# M8341X2.net
KiCad netlist of a schematic drawn in EAGLE
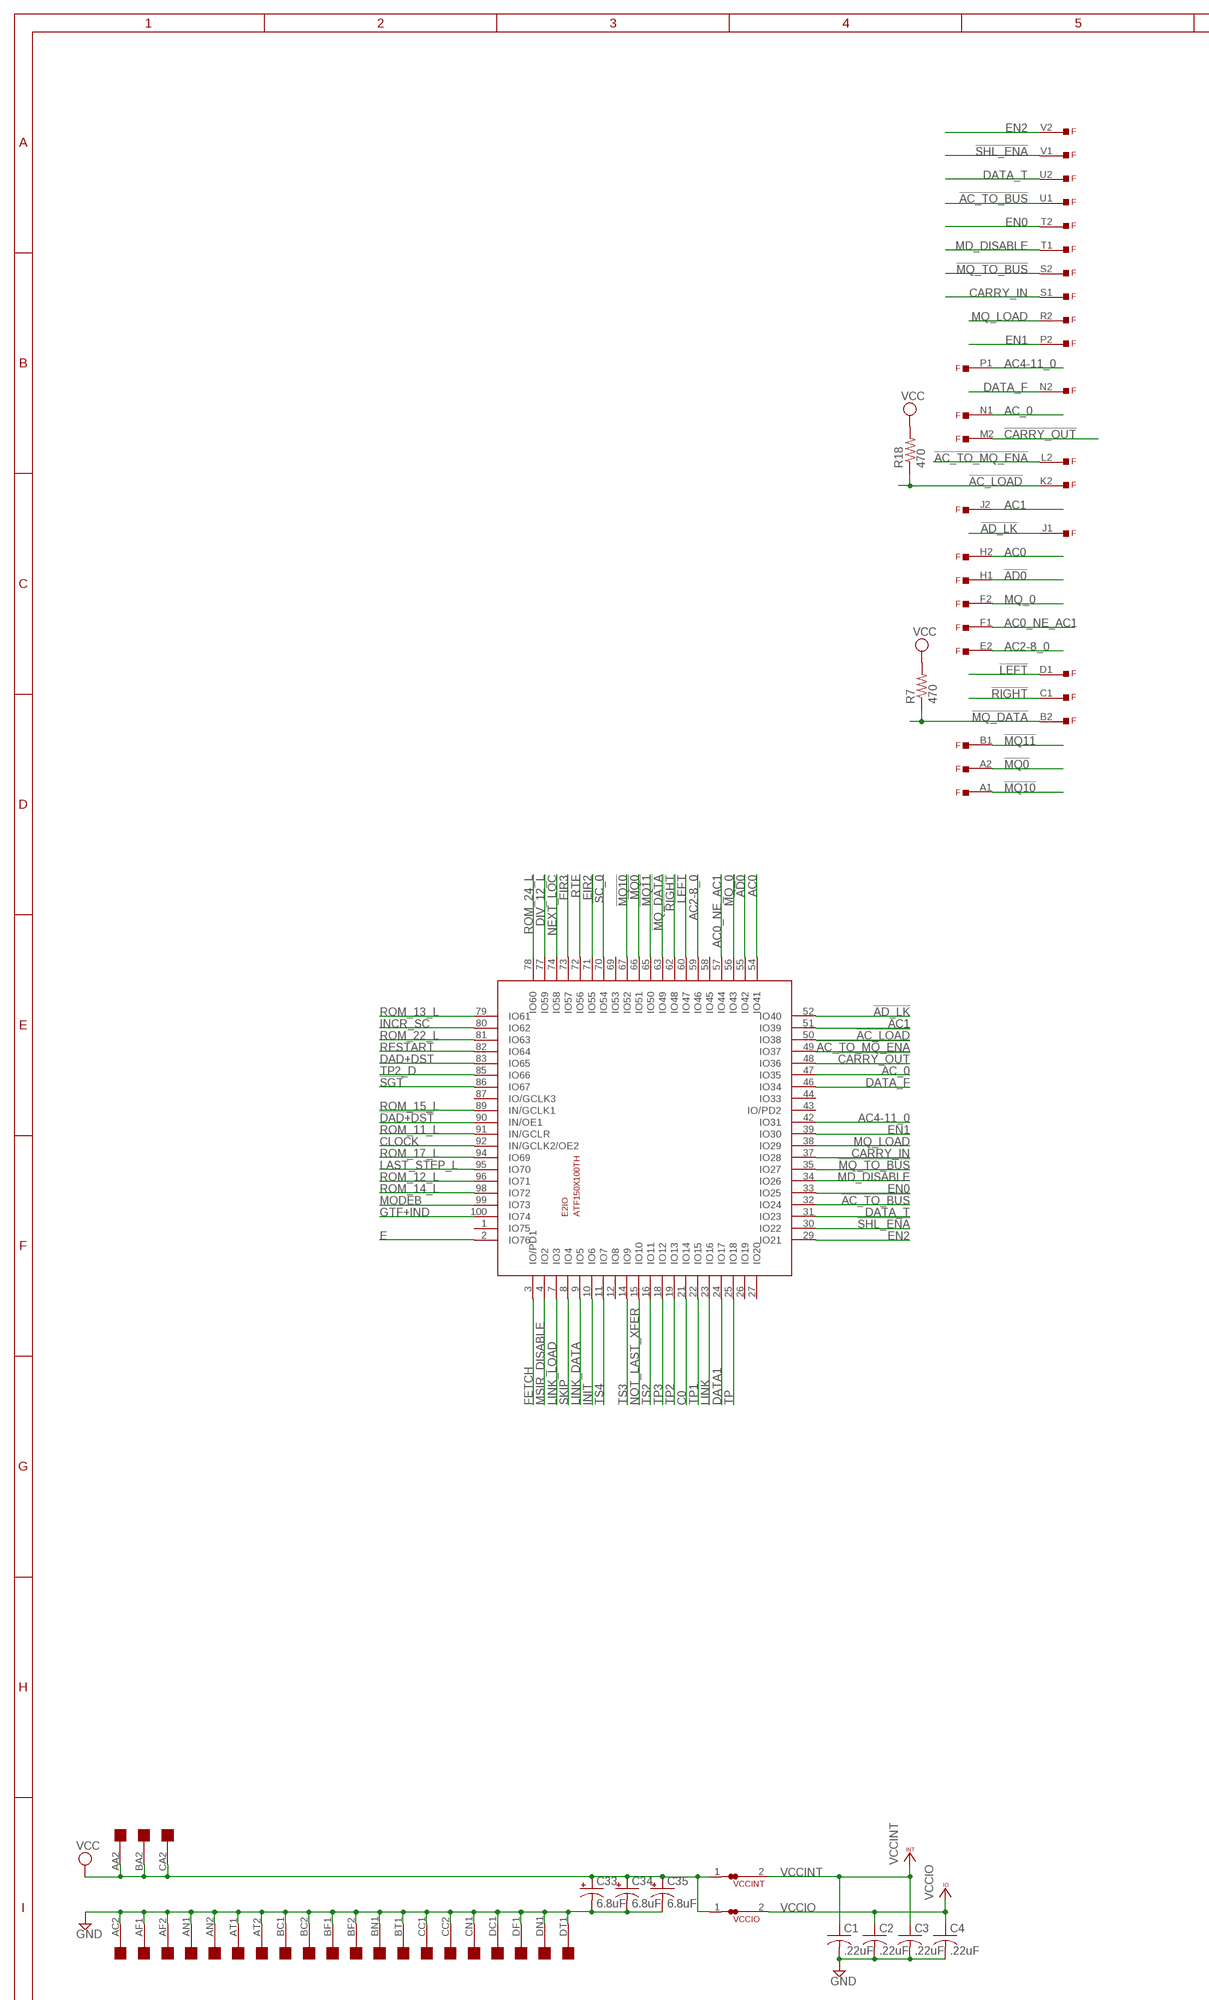
[diagram p0: schematic, sheet 1, part 1 of 2]
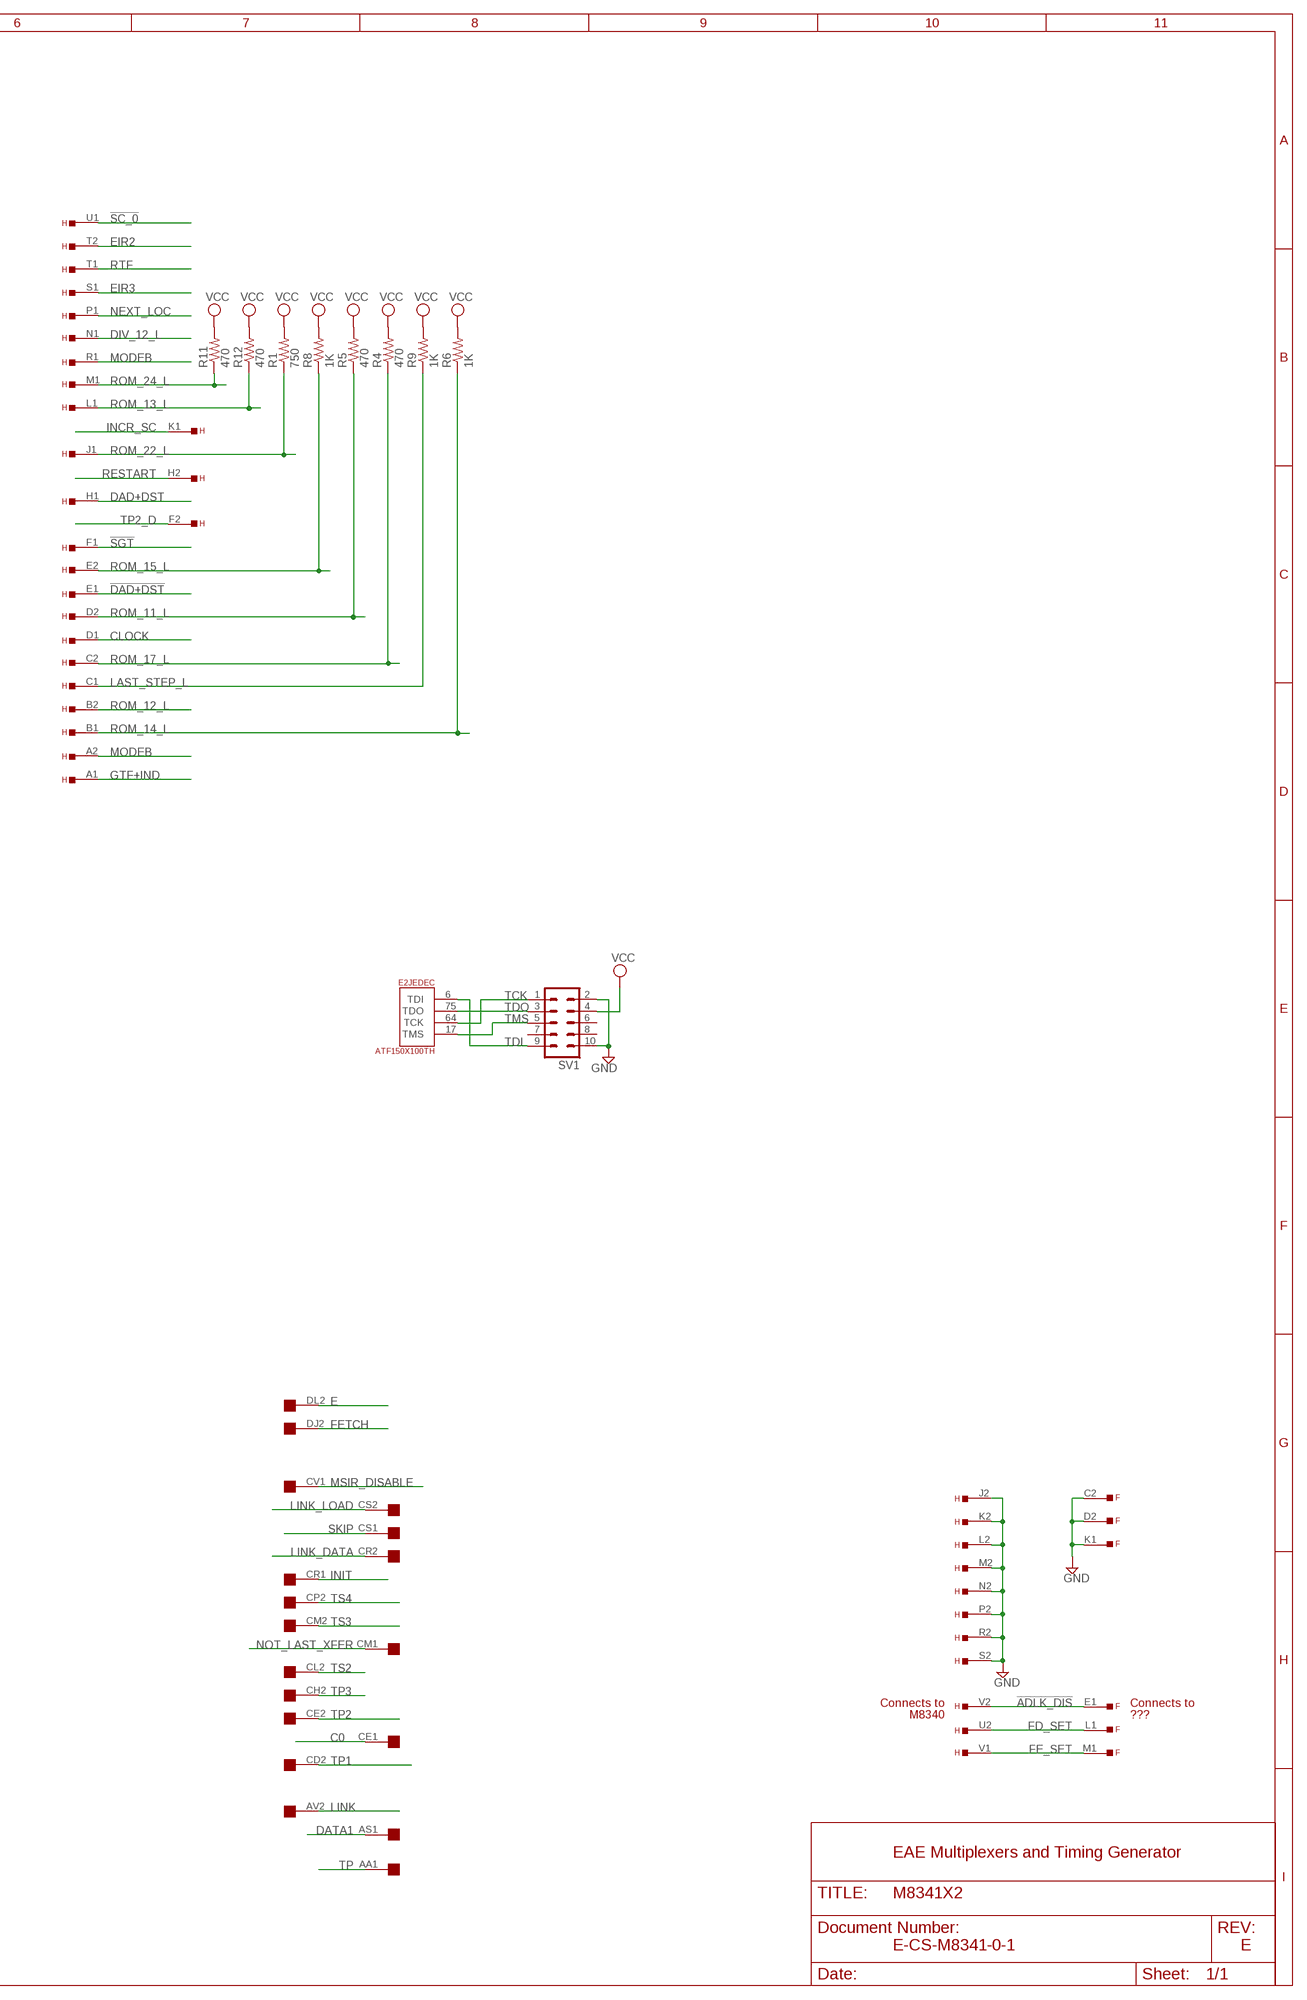
[diagram p1: schematic, sheet 1, part 2 of 2]

(export (version "E")
  (design (tool "Eeschema 10.0.6"))
  (components
    (comp (ref "C1")
      (value ".22uF")
      (footprint "eagle-import:C063-025X075")
      (libsource (lib "eagle-import") (part "C-US"))
    )
    (comp (ref "C2")
      (value ".22uF")
      (footprint "eagle-import:C063-025X075")
      (libsource (lib "eagle-import") (part "C-US"))
    )
    (comp (ref "C3")
      (value ".22uF")
      (footprint "eagle-import:C063-025X075")
      (libsource (lib "eagle-import") (part "C-US"))
    )
    (comp (ref "C4")
      (value ".22uF")
      (footprint "eagle-import:C063-025X075")
      (libsource (lib "eagle-import") (part "C-US"))
    )
    (comp (ref "C33")
      (value "6.8uF")
      (footprint "eagle-import:E12-8")
      (libsource (lib "eagle-import") (part "CPOL-USE20-8AXIAL"))
    )
    (comp (ref "C34")
      (value "6.8uF")
      (footprint "eagle-import:E12-8")
      (libsource (lib "eagle-import") (part "CPOL-USE20-8AXIAL"))
    )
    (comp (ref "C35")
      (value "6.8uF")
      (footprint "eagle-import:E12-8")
      (libsource (lib "eagle-import") (part "CPOL-USE20-8AXIAL"))
    )
    (comp (ref "E2")
      (value "ATF150X100TH")
      (footprint "eagle-import:TH-100")
      (libsource (lib "eagle-import") (part "ATF150X100TH"))
    )
    (comp (ref "F")
      (value "EDGE-TOP")
      (footprint "eagle-import:EDGE-CON2")
      (libsource (lib "eagle-import") (part "EDGE-TOP"))
    )
    (comp (ref "H")
      (value "EDGE-TOP")
      (footprint "eagle-import:EDGE-CON2")
      (libsource (lib "eagle-import") (part "EDGE-TOP"))
    )
    (comp (ref "R1")
      (value "750")
      (footprint "eagle-import:0207_10")
      (libsource (lib "eagle-import") (part "R-US_0207/10"))
    )
    (comp (ref "R4")
      (value "470")
      (footprint "eagle-import:0207_10")
      (libsource (lib "eagle-import") (part "R-US_0207/10"))
    )
    (comp (ref "R5")
      (value "470")
      (footprint "eagle-import:0207_10")
      (libsource (lib "eagle-import") (part "R-US_0207/10"))
    )
    (comp (ref "R6")
      (value "1K")
      (footprint "eagle-import:0207_10")
      (libsource (lib "eagle-import") (part "R-US_0207/10"))
    )
    (comp (ref "R7")
      (value "470")
      (footprint "eagle-import:0207_10")
      (libsource (lib "eagle-import") (part "R-US_0207/10"))
    )
    (comp (ref "R8")
      (value "1K")
      (footprint "eagle-import:0207_10")
      (libsource (lib "eagle-import") (part "R-US_0207/10"))
    )
    (comp (ref "R9")
      (value "1K")
      (footprint "eagle-import:0207_10")
      (libsource (lib "eagle-import") (part "R-US_0207/10"))
    )
    (comp (ref "R11")
      (value "470")
      (footprint "eagle-import:0207_10")
      (libsource (lib "eagle-import") (part "R-US_0207/10"))
    )
    (comp (ref "R12")
      (value "470")
      (footprint "eagle-import:0207_10")
      (libsource (lib "eagle-import") (part "R-US_0207/10"))
    )
    (comp (ref "R18")
      (value "470")
      (footprint "eagle-import:0207_10")
      (libsource (lib "eagle-import") (part "R-US_0207/10"))
    )
    (comp (ref "SV1")
      (value "ML10")
      (footprint "eagle-import:ML10")
      (libsource (lib "eagle-import") (part "ML10"))
    )
    (comp (ref "U$2")
      (value "QUAD")
      (footprint "eagle-import:EDGE-CON8")
      (libsource (lib "eagle-import") (part "QUAD"))
    )
    (comp (ref "VCCINT")
      (value "JUMPER-NC1")
      (footprint "eagle-import:NC1")
      (libsource (lib "eagle-import") (part "JUMPER-NC1"))
    )
    (comp (ref "VCCIO")
      (value "JUMPER-NC1")
      (footprint "eagle-import:NC1")
      (libsource (lib "eagle-import") (part "JUMPER-NC1"))
    )
  )
  (nets
    (net (code "1") (name "/AC0") (class "Default")
      (node (ref "E2") (pin "54") (pinfunction "IO41_54") (pintype "bidirectional"))
      (node (ref "F") (pin "H2") (pinfunction "P_H2") (pintype "passive"))
    )
    (net (code "2") (name "/AC0_NE_AC1") (class "Default")
      (node (ref "E2") (pin "57") (pinfunction "IO44_57") (pintype "bidirectional"))
      (node (ref "F") (pin "F1") (pinfunction "P_F1") (pintype "passive"))
    )
    (net (code "3") (name "/AC1") (class "Default")
      (node (ref "E2") (pin "51") (pinfunction "IO39_51") (pintype "bidirectional"))
      (node (ref "F") (pin "J2") (pinfunction "P_J2") (pintype "passive"))
    )
    (net (code "4") (name "/AC2-8_0") (class "Default")
      (node (ref "E2") (pin "59") (pinfunction "IO46_59") (pintype "bidirectional"))
      (node (ref "F") (pin "E2") (pinfunction "P_E2") (pintype "passive"))
    )
    (net (code "5") (name "/AC4-11_0") (class "Default")
      (node (ref "E2") (pin "42") (pinfunction "IO31_42") (pintype "bidirectional"))
      (node (ref "F") (pin "P1") (pinfunction "P_P1") (pintype "passive"))
    )
    (net (code "6") (name "/AC_0") (class "Default")
      (node (ref "E2") (pin "47") (pinfunction "IO35_47") (pintype "bidirectional"))
      (node (ref "F") (pin "N1") (pinfunction "P_N1") (pintype "passive"))
    )
    (net (code "7") (name "/C0") (class "Default")
      (node (ref "E2") (pin "21") (pinfunction "IO14_21") (pintype "bidirectional"))
      (node (ref "U$2") (pin "CE1") (pinfunction "1_CE1") (pintype "bidirectional"))
    )
    (net (code "8") (name "/CARRY_IN") (class "Default")
      (node (ref "E2") (pin "37") (pinfunction "IO28_37") (pintype "bidirectional"))
      (node (ref "F") (pin "S1") (pinfunction "P_S1") (pintype "passive"))
    )
    (net (code "9") (name "/CLOCK") (class "Default")
      (node (ref "E2") (pin "92") (pinfunction "IN/GCLK2/OE2_92") (pintype "input"))
      (node (ref "H") (pin "D1") (pinfunction "P_D1") (pintype "passive"))
    )
    (net (code "10") (name "/DAD+DST") (class "Default")
      (node (ref "E2") (pin "83") (pinfunction "IO65_83") (pintype "bidirectional"))
      (node (ref "H") (pin "H1") (pinfunction "P_H1") (pintype "passive"))
    )
    (net (code "11") (name "/DATA1") (class "Default")
      (node (ref "E2") (pin "24") (pinfunction "IO17_24") (pintype "bidirectional"))
      (node (ref "U$2") (pin "AS1") (pinfunction "1_AS1") (pintype "bidirectional"))
    )
    (net (code "12") (name "/DATA_F") (class "Default")
      (node (ref "E2") (pin "46") (pinfunction "IO34_46") (pintype "bidirectional"))
      (node (ref "F") (pin "N2") (pinfunction "P_N2") (pintype "passive"))
    )
    (net (code "13") (name "/DATA_T") (class "Default")
      (node (ref "E2") (pin "31") (pinfunction "IO23_31") (pintype "bidirectional"))
      (node (ref "F") (pin "U2") (pinfunction "P_U2") (pintype "passive"))
    )
    (net (code "14") (name "/DIV_12_L") (class "Default")
      (node (ref "E2") (pin "77") (pinfunction "IO59_77") (pintype "bidirectional"))
      (node (ref "H") (pin "N1") (pinfunction "P_N1") (pintype "passive"))
    )
    (net (code "15") (name "/E") (class "Default")
      (node (ref "E2") (pin "2") (pinfunction "IO76_2") (pintype "bidirectional"))
      (node (ref "U$2") (pin "DL2") (pinfunction "1_DL2") (pintype "bidirectional"))
    )
    (net (code "16") (name "/EIR2") (class "Default")
      (node (ref "E2") (pin "71") (pinfunction "IO55_71") (pintype "bidirectional"))
      (node (ref "H") (pin "T2") (pinfunction "P_T2") (pintype "passive"))
    )
    (net (code "17") (name "/EIR3") (class "Default")
      (node (ref "E2") (pin "73") (pinfunction "IO57_73") (pintype "bidirectional"))
      (node (ref "H") (pin "S1") (pinfunction "P_S1") (pintype "passive"))
    )
    (net (code "18") (name "/EN0") (class "Default")
      (node (ref "E2") (pin "33") (pinfunction "IO25_33") (pintype "bidirectional"))
      (node (ref "F") (pin "T2") (pinfunction "P_T2") (pintype "passive"))
    )
    (net (code "19") (name "/EN1") (class "Default")
      (node (ref "E2") (pin "39") (pinfunction "IO30_39") (pintype "bidirectional"))
      (node (ref "F") (pin "P2") (pinfunction "P_P2") (pintype "passive"))
    )
    (net (code "20") (name "/EN2") (class "Default")
      (node (ref "E2") (pin "29") (pinfunction "IO21_29") (pintype "bidirectional"))
      (node (ref "F") (pin "V2") (pinfunction "P_V2") (pintype "passive"))
    )
    (net (code "21") (name "/FD_SET") (class "Default")
      (node (ref "F") (pin "L1") (pinfunction "P_L1") (pintype "passive"))
      (node (ref "H") (pin "U2") (pinfunction "P_U2") (pintype "passive"))
    )
    (net (code "22") (name "/FETCH") (class "Default")
      (node (ref "E2") (pin "3") (pinfunction "IO/PD1_3") (pintype "bidirectional"))
      (node (ref "U$2") (pin "DJ2") (pinfunction "1_DJ2") (pintype "bidirectional"))
    )
    (net (code "23") (name "/FE_SET") (class "Default")
      (node (ref "F") (pin "M1") (pinfunction "P_M1") (pintype "passive"))
      (node (ref "H") (pin "V1") (pinfunction "P_V1") (pintype "passive"))
    )
    (net (code "24") (name "/GTF+IND") (class "Default")
      (node (ref "E2") (pin "100") (pinfunction "IO74_100") (pintype "bidirectional"))
      (node (ref "H") (pin "A1") (pinfunction "P_A1") (pintype "passive"))
    )
    (net (code "25") (name "/INCR_SC") (class "Default")
      (node (ref "E2") (pin "80") (pinfunction "IO62_80") (pintype "bidirectional"))
      (node (ref "H") (pin "K1") (pinfunction "P_K1") (pintype "passive"))
    )
    (net (code "26") (name "/INIT") (class "Default")
      (node (ref "E2") (pin "10") (pinfunction "IO6_10") (pintype "bidirectional"))
      (node (ref "U$2") (pin "CR1") (pinfunction "1_CR1") (pintype "bidirectional"))
    )
    (net (code "27") (name "/LAST_STEP_L") (class "Default")
      (node (ref "E2") (pin "95") (pinfunction "IO70_95") (pintype "bidirectional"))
      (node (ref "H") (pin "C1") (pinfunction "P_C1") (pintype "passive"))
      (node (ref "R9") (pin "1") (pinfunction "1_1") (pintype "passive"))
    )
    (net (code "28") (name "/LINK") (class "Default")
      (node (ref "E2") (pin "23") (pinfunction "IO16_23") (pintype "bidirectional"))
      (node (ref "U$2") (pin "AV2") (pinfunction "1_AV2") (pintype "bidirectional"))
    )
    (net (code "29") (name "/LINK_DATA") (class "Default")
      (node (ref "E2") (pin "9") (pinfunction "IO5_9") (pintype "bidirectional"))
      (node (ref "U$2") (pin "CR2") (pinfunction "1_CR2") (pintype "bidirectional"))
    )
    (net (code "30") (name "/LINK_LOAD") (class "Default")
      (node (ref "E2") (pin "7") (pinfunction "IO3_7") (pintype "bidirectional"))
      (node (ref "U$2") (pin "CS2") (pinfunction "1_CS2") (pintype "bidirectional"))
    )
    (net (code "31") (name "/MD_DISABLE") (class "Default")
      (node (ref "E2") (pin "34") (pinfunction "IO26_34") (pintype "bidirectional"))
      (node (ref "F") (pin "T1") (pinfunction "P_T1") (pintype "passive"))
    )
    (net (code "32") (name "/MODEB") (class "Default")
      (node (ref "E2") (pin "99") (pinfunction "IO73_99") (pintype "bidirectional"))
      (node (ref "H") (pin "A2") (pinfunction "P_A2") (pintype "passive"))
      (node (ref "H") (pin "R1") (pinfunction "P_R1") (pintype "passive"))
    )
    (net (code "33") (name "/MQ_0") (class "Default")
      (node (ref "E2") (pin "56") (pinfunction "IO43_56") (pintype "bidirectional"))
      (node (ref "F") (pin "F2") (pinfunction "P_F2") (pintype "passive"))
    )
    (net (code "34") (name "/MQ_LOAD") (class "Default")
      (node (ref "E2") (pin "38") (pinfunction "IO29_38") (pintype "bidirectional"))
      (node (ref "F") (pin "R2") (pinfunction "P_R2") (pintype "passive"))
    )
    (net (code "35") (name "/MSIR_DISABLE") (class "Default")
      (node (ref "E2") (pin "4") (pinfunction "IO2_4") (pintype "bidirectional"))
      (node (ref "U$2") (pin "CV1") (pinfunction "1_CV1") (pintype "bidirectional"))
    )
    (net (code "36") (name "/NEXT_LOC") (class "Default")
      (node (ref "E2") (pin "74") (pinfunction "IO58_74") (pintype "bidirectional"))
      (node (ref "H") (pin "P1") (pinfunction "P_P1") (pintype "passive"))
    )
    (net (code "37") (name "/NOT_LAST_XFER") (class "Default")
      (node (ref "E2") (pin "15") (pinfunction "IO10_15") (pintype "bidirectional"))
      (node (ref "U$2") (pin "CM1") (pinfunction "1_CM1") (pintype "bidirectional"))
    )
    (net (code "38") (name "/RESTART") (class "Default")
      (node (ref "E2") (pin "82") (pinfunction "IO64_82") (pintype "bidirectional"))
      (node (ref "H") (pin "H2") (pinfunction "P_H2") (pintype "passive"))
    )
    (net (code "39") (name "/ROM_11_L") (class "Default")
      (node (ref "E2") (pin "91") (pinfunction "IN/GCLR_91") (pintype "input"))
      (node (ref "H") (pin "D2") (pinfunction "P_D2") (pintype "passive"))
      (node (ref "R5") (pin "1") (pinfunction "1_1") (pintype "passive"))
    )
    (net (code "40") (name "/ROM_12_L") (class "Default")
      (node (ref "E2") (pin "96") (pinfunction "IO71_96") (pintype "bidirectional"))
      (node (ref "H") (pin "B2") (pinfunction "P_B2") (pintype "passive"))
    )
    (net (code "41") (name "/ROM_13_L") (class "Default")
      (node (ref "E2") (pin "79") (pinfunction "IO61_79") (pintype "bidirectional"))
      (node (ref "H") (pin "L1") (pinfunction "P_L1") (pintype "passive"))
      (node (ref "R12") (pin "1") (pinfunction "1_1") (pintype "passive"))
    )
    (net (code "42") (name "/ROM_14_L") (class "Default")
      (node (ref "E2") (pin "98") (pinfunction "IO72_98") (pintype "bidirectional"))
      (node (ref "H") (pin "B1") (pinfunction "P_B1") (pintype "passive"))
      (node (ref "R6") (pin "1") (pinfunction "1_1") (pintype "passive"))
    )
    (net (code "43") (name "/ROM_15_L") (class "Default")
      (node (ref "E2") (pin "89") (pinfunction "IN/GCLK1_89") (pintype "input"))
      (node (ref "H") (pin "E2") (pinfunction "P_E2") (pintype "passive"))
      (node (ref "R8") (pin "1") (pinfunction "1_1") (pintype "passive"))
    )
    (net (code "44") (name "/ROM_17_L") (class "Default")
      (node (ref "E2") (pin "94") (pinfunction "IO69_94") (pintype "bidirectional"))
      (node (ref "H") (pin "C2") (pinfunction "P_C2") (pintype "passive"))
      (node (ref "R4") (pin "1") (pinfunction "1_1") (pintype "passive"))
    )
    (net (code "45") (name "/ROM_22_L") (class "Default")
      (node (ref "E2") (pin "81") (pinfunction "IO63_81") (pintype "bidirectional"))
      (node (ref "H") (pin "J1") (pinfunction "P_J1") (pintype "passive"))
      (node (ref "R1") (pin "1") (pinfunction "1_1") (pintype "passive"))
    )
    (net (code "46") (name "/ROM_24_L") (class "Default")
      (node (ref "E2") (pin "78") (pinfunction "IO60_78") (pintype "bidirectional"))
      (node (ref "H") (pin "M1") (pinfunction "P_M1") (pintype "passive"))
      (node (ref "R11") (pin "1") (pinfunction "1_1") (pintype "passive"))
    )
    (net (code "47") (name "/RTF") (class "Default")
      (node (ref "E2") (pin "72") (pinfunction "IO56_72") (pintype "bidirectional"))
      (node (ref "H") (pin "T1") (pinfunction "P_T1") (pintype "passive"))
    )
    (net (code "48") (name "/SKIP") (class "Default")
      (node (ref "E2") (pin "8") (pinfunction "IO4_8") (pintype "bidirectional"))
      (node (ref "U$2") (pin "CS1") (pinfunction "1_CS1") (pintype "bidirectional"))
    )
    (net (code "49") (name "/TCK") (class "Default")
      (node (ref "E2") (pin "64") (pinfunction "TCK_64") (pintype "bidirectional"))
      (node (ref "SV1") (pin "1") (pinfunction "1_1") (pintype "passive"))
    )
    (net (code "50") (name "/TDI") (class "Default")
      (node (ref "E2") (pin "6") (pinfunction "TDI_6") (pintype "bidirectional"))
      (node (ref "SV1") (pin "9") (pinfunction "9_9") (pintype "passive"))
    )
    (net (code "51") (name "/TDO") (class "Default")
      (node (ref "E2") (pin "75") (pinfunction "TDO_75") (pintype "bidirectional"))
      (node (ref "SV1") (pin "3") (pinfunction "3_3") (pintype "passive"))
    )
    (net (code "52") (name "/TMS") (class "Default")
      (node (ref "E2") (pin "17") (pinfunction "TMS_17") (pintype "bidirectional"))
      (node (ref "SV1") (pin "5") (pinfunction "5_5") (pintype "passive"))
    )
    (net (code "53") (name "/TP") (class "Default")
      (node (ref "E2") (pin "25") (pinfunction "IO18_25") (pintype "bidirectional"))
      (node (ref "U$2") (pin "AA1") (pinfunction "1_AA1") (pintype "bidirectional"))
    )
    (net (code "54") (name "/TP1") (class "Default")
      (node (ref "E2") (pin "22") (pinfunction "IO15_22") (pintype "bidirectional"))
      (node (ref "U$2") (pin "CD2") (pinfunction "1_CD2") (pintype "bidirectional"))
    )
    (net (code "55") (name "/TP2") (class "Default")
      (node (ref "E2") (pin "19") (pinfunction "IO13_19") (pintype "bidirectional"))
      (node (ref "U$2") (pin "CE2") (pinfunction "1_CE2") (pintype "bidirectional"))
    )
    (net (code "56") (name "/TP2_D") (class "Default")
      (node (ref "E2") (pin "85") (pinfunction "IO66_85") (pintype "bidirectional"))
      (node (ref "H") (pin "F2") (pinfunction "P_F2") (pintype "passive"))
    )
    (net (code "57") (name "/TP3") (class "Default")
      (node (ref "E2") (pin "18") (pinfunction "IO12_18") (pintype "bidirectional"))
      (node (ref "U$2") (pin "CH2") (pinfunction "1_CH2") (pintype "bidirectional"))
    )
    (net (code "58") (name "/TS2") (class "Default")
      (node (ref "E2") (pin "16") (pinfunction "IO11_16") (pintype "bidirectional"))
      (node (ref "U$2") (pin "CL2") (pinfunction "1_CL2") (pintype "bidirectional"))
    )
    (net (code "59") (name "/TS3") (class "Default")
      (node (ref "E2") (pin "14") (pinfunction "IO9_14") (pintype "bidirectional"))
      (node (ref "U$2") (pin "CM2") (pinfunction "1_CM2") (pintype "bidirectional"))
    )
    (net (code "60") (name "/TS4") (class "Default")
      (node (ref "E2") (pin "11") (pinfunction "IO7_11") (pintype "bidirectional"))
      (node (ref "U$2") (pin "CP2") (pinfunction "1_CP2") (pintype "bidirectional"))
    )
    (net (code "61") (name "/~{AC_LOAD}") (class "Default")
      (node (ref "E2") (pin "50") (pinfunction "IO38_50") (pintype "bidirectional"))
      (node (ref "F") (pin "K2") (pinfunction "P_K2") (pintype "passive"))
      (node (ref "R18") (pin "1") (pinfunction "1_1") (pintype "passive"))
    )
    (net (code "62") (name "/~{AC_TO_BUS}") (class "Default")
      (node (ref "E2") (pin "32") (pinfunction "IO24_32") (pintype "bidirectional"))
      (node (ref "F") (pin "U1") (pinfunction "P_U1") (pintype "passive"))
    )
    (net (code "63") (name "/~{AC_TO_MQ_ENA}") (class "Default")
      (node (ref "E2") (pin "49") (pinfunction "IO37_49") (pintype "bidirectional"))
      (node (ref "F") (pin "L2") (pinfunction "P_L2") (pintype "passive"))
    )
    (net (code "64") (name "/~{AD0}") (class "Default")
      (node (ref "E2") (pin "55") (pinfunction "IO42_55") (pintype "bidirectional"))
      (node (ref "F") (pin "H1") (pinfunction "P_H1") (pintype "passive"))
    )
    (net (code "65") (name "/~{ADLK_DIS}") (class "Default")
      (node (ref "F") (pin "E1") (pinfunction "P_E1") (pintype "passive"))
      (node (ref "H") (pin "V2") (pinfunction "P_V2") (pintype "passive"))
    )
    (net (code "66") (name "/~{AD_LK}") (class "Default")
      (node (ref "E2") (pin "52") (pinfunction "IO40_52") (pintype "bidirectional"))
      (node (ref "F") (pin "J1") (pinfunction "P_J1") (pintype "passive"))
    )
    (net (code "67") (name "/~{CARRY_OUT}") (class "Default")
      (node (ref "E2") (pin "48") (pinfunction "IO36_48") (pintype "bidirectional"))
      (node (ref "F") (pin "M2") (pinfunction "P_M2") (pintype "passive"))
    )
    (net (code "68") (name "/~{DAD+DST}") (class "Default")
      (node (ref "E2") (pin "90") (pinfunction "IN/OE1_90") (pintype "input"))
      (node (ref "H") (pin "E1") (pinfunction "P_E1") (pintype "passive"))
    )
    (net (code "69") (name "/~{LEFT}") (class "Default")
      (node (ref "E2") (pin "60") (pinfunction "IO47_60") (pintype "bidirectional"))
      (node (ref "F") (pin "D1") (pinfunction "P_D1") (pintype "passive"))
    )
    (net (code "70") (name "/~{MQ0}") (class "Default")
      (node (ref "E2") (pin "66") (pinfunction "IO51_66") (pintype "bidirectional"))
      (node (ref "F") (pin "A2") (pinfunction "P_A2") (pintype "passive"))
    )
    (net (code "71") (name "/~{MQ10}") (class "Default")
      (node (ref "E2") (pin "67") (pinfunction "IO52_67") (pintype "bidirectional"))
      (node (ref "F") (pin "A1") (pinfunction "P_A1") (pintype "passive"))
    )
    (net (code "72") (name "/~{MQ11}") (class "Default")
      (node (ref "E2") (pin "65") (pinfunction "IO50_65") (pintype "bidirectional"))
      (node (ref "F") (pin "B1") (pinfunction "P_B1") (pintype "passive"))
    )
    (net (code "73") (name "/~{MQ_DATA}") (class "Default")
      (node (ref "E2") (pin "63") (pinfunction "IO49_63") (pintype "bidirectional"))
      (node (ref "F") (pin "B2") (pinfunction "P_B2") (pintype "passive"))
      (node (ref "R7") (pin "1") (pinfunction "1_1") (pintype "passive"))
    )
    (net (code "74") (name "/~{MQ_TO_BUS}") (class "Default")
      (node (ref "E2") (pin "35") (pinfunction "IO27_35") (pintype "bidirectional"))
      (node (ref "F") (pin "S2") (pinfunction "P_S2") (pintype "passive"))
    )
    (net (code "75") (name "/~{RIGHT}") (class "Default")
      (node (ref "E2") (pin "62") (pinfunction "IO48_62") (pintype "bidirectional"))
      (node (ref "F") (pin "C1") (pinfunction "P_C1") (pintype "passive"))
    )
    (net (code "76") (name "/~{SC_0}") (class "Default")
      (node (ref "E2") (pin "70") (pinfunction "IO54_70") (pintype "bidirectional"))
      (node (ref "H") (pin "U1") (pinfunction "P_U1") (pintype "passive"))
    )
    (net (code "77") (name "/~{SGT}") (class "Default")
      (node (ref "E2") (pin "86") (pinfunction "IO67_86") (pintype "bidirectional"))
      (node (ref "H") (pin "F1") (pinfunction "P_F1") (pintype "passive"))
    )
    (net (code "78") (name "/~{SHL_ENA}") (class "Default")
      (node (ref "E2") (pin "30") (pinfunction "IO22_30") (pintype "bidirectional"))
      (node (ref "F") (pin "V1") (pinfunction "P_V1") (pintype "passive"))
    )
    (net (code "79") (name "GND") (class "Default")
      (node (ref "C1") (pin "2") (pinfunction "2_2") (pintype "passive"))
      (node (ref "C2") (pin "2") (pinfunction "2_2") (pintype "passive"))
      (node (ref "C3") (pin "2") (pinfunction "2_2") (pintype "passive"))
      (node (ref "C33") (pin "-") (pinfunction "-_-") (pintype "passive"))
      (node (ref "C34") (pin "-") (pinfunction "-_-") (pintype "passive"))
      (node (ref "C35") (pin "-") (pinfunction "-_-") (pintype "passive"))
      (node (ref "C4") (pin "2") (pinfunction "2_2") (pintype "passive"))
      (node (ref "F") (pin "C2") (pinfunction "P_C2") (pintype "passive"))
      (node (ref "F") (pin "D2") (pinfunction "P_D2") (pintype "passive"))
      (node (ref "F") (pin "K1") (pinfunction "P_K1") (pintype "passive"))
      (node (ref "H") (pin "J2") (pinfunction "P_J2") (pintype "passive"))
      (node (ref "H") (pin "K2") (pinfunction "P_K2") (pintype "passive"))
      (node (ref "H") (pin "L2") (pinfunction "P_L2") (pintype "passive"))
      (node (ref "H") (pin "M2") (pinfunction "P_M2") (pintype "passive"))
      (node (ref "H") (pin "N2") (pinfunction "P_N2") (pintype "passive"))
      (node (ref "H") (pin "P2") (pinfunction "P_P2") (pintype "passive"))
      (node (ref "H") (pin "R2") (pinfunction "P_R2") (pintype "passive"))
      (node (ref "H") (pin "S2") (pinfunction "P_S2") (pintype "passive"))
      (node (ref "SV1") (pin "10") (pinfunction "10_10") (pintype "passive"))
      (node (ref "SV1") (pin "2") (pinfunction "2_2") (pintype "passive"))
      (node (ref "U$2") (pin "AC2") (pinfunction "1_AC2") (pintype "bidirectional"))
      (node (ref "U$2") (pin "AF1") (pinfunction "1_AF1") (pintype "bidirectional"))
      (node (ref "U$2") (pin "AF2") (pinfunction "1_AF2") (pintype "bidirectional"))
      (node (ref "U$2") (pin "AN1") (pinfunction "1_AN1") (pintype "bidirectional"))
      (node (ref "U$2") (pin "AN2") (pinfunction "1_AN2") (pintype "bidirectional"))
      (node (ref "U$2") (pin "AT1") (pinfunction "1_AT1") (pintype "bidirectional"))
      (node (ref "U$2") (pin "AT2") (pinfunction "1_AT2") (pintype "bidirectional"))
      (node (ref "U$2") (pin "BC1") (pinfunction "1_BC1") (pintype "bidirectional"))
      (node (ref "U$2") (pin "BC2") (pinfunction "1_BC2") (pintype "bidirectional"))
      (node (ref "U$2") (pin "BF1") (pinfunction "1_BF1") (pintype "bidirectional"))
      (node (ref "U$2") (pin "BF2") (pinfunction "1_BF2") (pintype "bidirectional"))
      (node (ref "U$2") (pin "BN1") (pinfunction "1_BN1") (pintype "bidirectional"))
      (node (ref "U$2") (pin "BT1") (pinfunction "1_BT1") (pintype "bidirectional"))
      (node (ref "U$2") (pin "CC1") (pinfunction "1_CC1") (pintype "bidirectional"))
      (node (ref "U$2") (pin "CC2") (pinfunction "1_CC2") (pintype "bidirectional"))
      (node (ref "U$2") (pin "CN1") (pinfunction "1_CN1") (pintype "bidirectional"))
      (node (ref "U$2") (pin "DC1") (pinfunction "1_DC1") (pintype "bidirectional"))
      (node (ref "U$2") (pin "DF1") (pinfunction "1_DF1") (pintype "bidirectional"))
      (node (ref "U$2") (pin "DN1") (pinfunction "1_DN1") (pintype "bidirectional"))
      (node (ref "U$2") (pin "DT1") (pinfunction "1_DT1") (pintype "bidirectional"))
    )
    (net (code "80") (name "VCC") (class "Default")
      (node (ref "C33") (pin "+") (pinfunction "+_+") (pintype "passive"))
      (node (ref "C34") (pin "+") (pinfunction "+_+") (pintype "passive"))
      (node (ref "C35") (pin "+") (pinfunction "+_+") (pintype "passive"))
      (node (ref "R1") (pin "2") (pinfunction "2_2") (pintype "passive"))
      (node (ref "R11") (pin "2") (pinfunction "2_2") (pintype "passive"))
      (node (ref "R12") (pin "2") (pinfunction "2_2") (pintype "passive"))
      (node (ref "R18") (pin "2") (pinfunction "2_2") (pintype "passive"))
      (node (ref "R4") (pin "2") (pinfunction "2_2") (pintype "passive"))
      (node (ref "R5") (pin "2") (pinfunction "2_2") (pintype "passive"))
      (node (ref "R6") (pin "2") (pinfunction "2_2") (pintype "passive"))
      (node (ref "R7") (pin "2") (pinfunction "2_2") (pintype "passive"))
      (node (ref "R8") (pin "2") (pinfunction "2_2") (pintype "passive"))
      (node (ref "R9") (pin "2") (pinfunction "2_2") (pintype "passive"))
      (node (ref "SV1") (pin "4") (pinfunction "4_4") (pintype "passive"))
      (node (ref "U$2") (pin "AA2") (pinfunction "1_AA2") (pintype "bidirectional"))
      (node (ref "U$2") (pin "BA2") (pinfunction "1_BA2") (pintype "bidirectional"))
      (node (ref "U$2") (pin "CA2") (pinfunction "1_CA2") (pintype "bidirectional"))
      (node (ref "VCCINT") (pin "1") (pinfunction "1_1") (pintype "bidirectional"))
      (node (ref "VCCIO") (pin "1") (pinfunction "1_1") (pintype "bidirectional"))
    )
    (net (code "81") (name "VCCINT") (class "Default")
      (node (ref "C1") (pin "1") (pinfunction "1_1") (pintype "passive"))
      (node (ref "C3") (pin "1") (pinfunction "1_1") (pintype "passive"))
      (node (ref "VCCINT") (pin "2") (pinfunction "2_2") (pintype "bidirectional"))
    )
    (net (code "82") (name "VCCIO") (class "Default")
      (node (ref "C2") (pin "1") (pinfunction "1_1") (pintype "passive"))
      (node (ref "C4") (pin "1") (pinfunction "1_1") (pintype "passive"))
      (node (ref "VCCIO") (pin "2") (pinfunction "2_2") (pintype "bidirectional"))
    )
    (net (code "83") (name "unconnected-(E2Q-IO8-Pad12)") (class "Default")
      (node (ref "E2") (pin "12") (pinfunction "IO8_12") (pintype "bidirectional"))
    )
    (net (code "84") (name "unconnected-(E2Q-IO19-Pad26)") (class "Default")
      (node (ref "E2") (pin "26") (pinfunction "IO19_26") (pintype "bidirectional"))
    )
    (net (code "85") (name "unconnected-(E2Q-IO20-Pad27)") (class "Default")
      (node (ref "E2") (pin "27") (pinfunction "IO20_27") (pintype "bidirectional"))
    )
    (net (code "86") (name "unconnected-(E2Q-IO33-Pad44)") (class "Default")
      (node (ref "E2") (pin "44") (pinfunction "IO33_44") (pintype "bidirectional"))
    )
    (net (code "87") (name "unconnected-(E2Q-IO45-Pad58)") (class "Default")
      (node (ref "E2") (pin "58") (pinfunction "IO45_58") (pintype "bidirectional"))
    )
    (net (code "88") (name "unconnected-(E2Q-IO53-Pad69)") (class "Default")
      (node (ref "E2") (pin "69") (pinfunction "IO53_69") (pintype "bidirectional"))
    )
    (net (code "89") (name "unconnected-(E2Q-IO75-Pad1)") (class "Default")
      (node (ref "E2") (pin "1") (pinfunction "IO75_1") (pintype "bidirectional"))
    )
    (net (code "90") (name "unconnected-(E2Q-IO{slash}GCLK3-Pad87)") (class "Default")
      (node (ref "E2") (pin "87") (pinfunction "IO/GCLK3_87") (pintype "bidirectional"))
    )
    (net (code "91") (name "unconnected-(E2Q-IO{slash}PD2-Pad43)") (class "Default")
      (node (ref "E2") (pin "43") (pinfunction "IO/PD2_43") (pintype "bidirectional"))
    )
    (net (code "92") (name "unconnected-(SV1-Pad6)") (class "Default")
      (node (ref "SV1") (pin "6") (pinfunction "6_6") (pintype "passive"))
    )
    (net (code "93") (name "unconnected-(SV1-Pad7)") (class "Default")
      (node (ref "SV1") (pin "7") (pinfunction "7_7") (pintype "passive"))
    )
    (net (code "94") (name "unconnected-(SV1-Pad8)") (class "Default")
      (node (ref "SV1") (pin "8") (pinfunction "8_8") (pintype "passive"))
    )
  )
)
